# CustomTP4056Module.net
KiCad netlist of a schematic drawn in Altium Designer
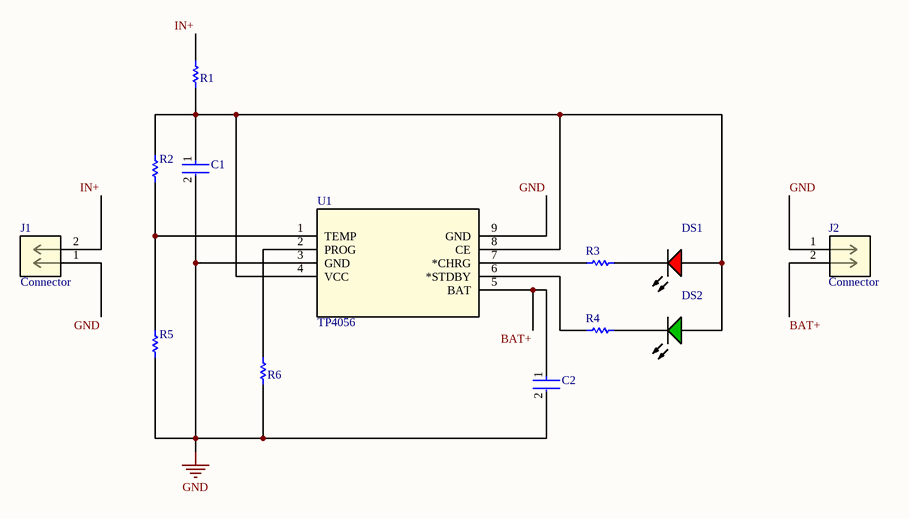
[diagram p0: CustomTP4056Module.SchDoc]

(export (version "E")
  (design (tool "Eeschema 10.0.6"))
  (components
    (comp (ref "C1")
      (value "GRM188R60J106ME47D")
      (footprint "FP-GRM188-0_1-e0_2_0_55-IPC_A")
      (description "Chip Multilayer Ceramic Capacitors for General Purpose, 0603, 10uF, X5R, 15%, 20%, 6.3V")
      (fields (field (name "VOLTAGE") "6.3V") (field (name "TOLERANCE") "20%"))
      (libsource (lib "Altium Content Vault") (part "02cd4be3c70576c341d710602a673aa"))
    )
    (comp (ref "C2")
      (value "GRM188R60J106ME47D")
      (footprint "FP-GRM188-0_1-e0_2_0_55-IPC_A")
      (description "Chip Multilayer Ceramic Capacitors for General Purpose, 0603, 10uF, X5R, 15%, 20%, 6.3V")
      (fields (field (name "VOLTAGE") "6.3V") (field (name "TOLERANCE") "20%"))
      (libsource (lib "Altium Content Vault") (part "02cd4be3c70576c341d710602a673aa"))
    )
    (comp (ref "DS1")
      (value "LTST-C170KRKT")
      (footprint "LTST-C170KRKT_V")
      (description "LED Red, 75 mW, 54 mcd, -55 to 85 degC, 2-Pin SMD, RoHS, Tape and Reel")
      (fields (field (name "MANUFACTURER") "Lite-On"))
      (libsource (lib "Altium Content Vault") (part "LED-RED-AK-2"))
    )
    (comp (ref "DS2")
      (value "LTST-C170KGKT")
      (footprint "LTST-LTST-C170KGKT-2_V")
      (description "Ultra Bright AlInGaP Chip LED, 75 mW, -55 to 85 degC, 2-Pin SMD (0805), RoHS, Tape and Reel")
      (fields (field (name "MANUFACTURER") "Lite-On"))
      (libsource (lib "Altium Content Vault") (part "LED-GREEN-KA-2"))
    )
    (comp (ref "J1")
      (value "Connector")
      (footprint "CONN_M20-99902_HRW")
      (description "No Description Available")
      (libsource (lib "") (part "M20-9990245_1"))
    )
    (comp (ref "J2")
      (value "Connector")
      (footprint "CONN_M20-99902_HRW")
      (description "No Description Available")
      (libsource (lib "M20-9990245") (part "M20-9990245"))
    )
    (comp (ref "R1")
      (value "ERJ6ENF2200V")
      (footprint "RESC2013X70X40NL20T20")
      (fields (field (name "MANUFACTURER") "Panasonic"))
      (libsource (lib "Altium Content Vault") (part "RES"))
    )
    (comp (ref "R2")
      (value "ERJ6ENF2200V")
      (footprint "RESC2013X70X40NL20T20")
      (fields (field (name "MANUFACTURER") "Panasonic"))
      (libsource (lib "Altium Content Vault") (part "RES"))
    )
    (comp (ref "R3")
      (value "ERJ6ENF2200V")
      (footprint "RESC2013X70X40NL20T20")
      (fields (field (name "MANUFACTURER") "Panasonic"))
      (libsource (lib "Altium Content Vault") (part "RES"))
    )
    (comp (ref "R4")
      (value "ERJ6ENF2200V")
      (footprint "RESC2013X70X40NL20T20")
      (fields (field (name "MANUFACTURER") "Panasonic"))
      (libsource (lib "Altium Content Vault") (part "RES"))
    )
    (comp (ref "R5")
      (value "ERJ6ENF2200V")
      (footprint "RESC2013X70X40NL20T20")
      (fields (field (name "MANUFACTURER") "Panasonic"))
      (libsource (lib "Altium Content Vault") (part "RES"))
    )
    (comp (ref "R6")
      (value "ERJ6ENF2200V")
      (footprint "RESC2013X70X40NL20T20")
      (fields (field (name "MANUFACTURER") "Panasonic"))
      (libsource (lib "Altium Content Vault") (part "RES"))
    )
    (comp (ref "U1")
      (value "TP4056")
      (footprint "ESOP8_TPW")
      (description "No Description Available")
      (libsource (lib "TP4056") (part "TP4056"))
    )
  )
  (nets
    (net (code "1") (name "/BAT+") (class "Default")
      (node (ref "C2") (pin "1") (pinfunction "1_1") (pintype "passive"))
      (node (ref "J2") (pin "2") (pinfunction "2_2") (pintype "passive"))
      (node (ref "U1") (pin "5") (pinfunction "BAT_5") (pintype "passive"))
    )
    (net (code "2") (name "/IN+") (class "Default")
      (node (ref "J1") (pin "2") (pinfunction "2_2") (pintype "passive"))
      (node (ref "R1") (pin "2") (pinfunction "2_2") (pintype "passive"))
    )
    (net (code "3") (name "GND") (class "Default")
      (node (ref "C1") (pin "2") (pinfunction "2_2") (pintype "passive"))
      (node (ref "C2") (pin "2") (pinfunction "2_2") (pintype "passive"))
      (node (ref "J1") (pin "1") (pinfunction "1_1") (pintype "passive"))
      (node (ref "J2") (pin "1") (pinfunction "1_1") (pintype "passive"))
      (node (ref "R5") (pin "1") (pinfunction "1_1") (pintype "passive"))
      (node (ref "R6") (pin "2") (pinfunction "2_2") (pintype "passive"))
      (node (ref "U1") (pin "3") (pinfunction "GND_3") (pintype "power_in"))
      (node (ref "U1") (pin "9") (pinfunction "GND_9") (pintype "power_in"))
    )
    (net (code "4") (name "Net-(DS1-A)") (class "Default")
      (node (ref "C1") (pin "1") (pinfunction "1_1") (pintype "passive"))
      (node (ref "DS1") (pin "1") (pinfunction "A_1") (pintype "passive"))
      (node (ref "DS2") (pin "2") (pinfunction "A_2") (pintype "passive"))
      (node (ref "R1") (pin "1") (pinfunction "1_1") (pintype "passive"))
      (node (ref "R2") (pin "2") (pinfunction "2_2") (pintype "passive"))
      (node (ref "U1") (pin "4") (pinfunction "VCC_4") (pintype "power_in"))
      (node (ref "U1") (pin "8") (pinfunction "CE_8") (pintype "passive"))
    )
    (net (code "5") (name "Net-(DS1-K)") (class "Default")
      (node (ref "DS1") (pin "2") (pinfunction "K_2") (pintype "passive"))
      (node (ref "R3") (pin "2") (pinfunction "2_2") (pintype "passive"))
    )
    (net (code "6") (name "Net-(DS2-K)") (class "Default")
      (node (ref "DS2") (pin "1") (pinfunction "K_1") (pintype "passive"))
      (node (ref "R4") (pin "2") (pinfunction "2_2") (pintype "passive"))
    )
    (net (code "7") (name "Net-(U1-*CHRG)") (class "Default")
      (node (ref "R3") (pin "1") (pinfunction "1_1") (pintype "passive"))
      (node (ref "U1") (pin "7") (pinfunction "*CHRG_7") (pintype "passive"))
    )
    (net (code "8") (name "Net-(U1-*STDBY)") (class "Default")
      (node (ref "R4") (pin "1") (pinfunction "1_1") (pintype "passive"))
      (node (ref "U1") (pin "6") (pinfunction "*STDBY_6") (pintype "passive"))
    )
    (net (code "9") (name "Net-(U1-PROG)") (class "Default")
      (node (ref "R6") (pin "1") (pinfunction "1_1") (pintype "passive"))
      (node (ref "U1") (pin "2") (pinfunction "PROG_2") (pintype "passive"))
    )
    (net (code "10") (name "Net-(U1-TEMP)") (class "Default")
      (node (ref "R2") (pin "1") (pinfunction "1_1") (pintype "passive"))
      (node (ref "R5") (pin "2") (pinfunction "2_2") (pintype "passive"))
      (node (ref "U1") (pin "1") (pinfunction "TEMP_1") (pintype "passive"))
    )
  )
)
